# eVV_Power_Supply.net
KiCad netlist of a schematic drawn in Altium Designer
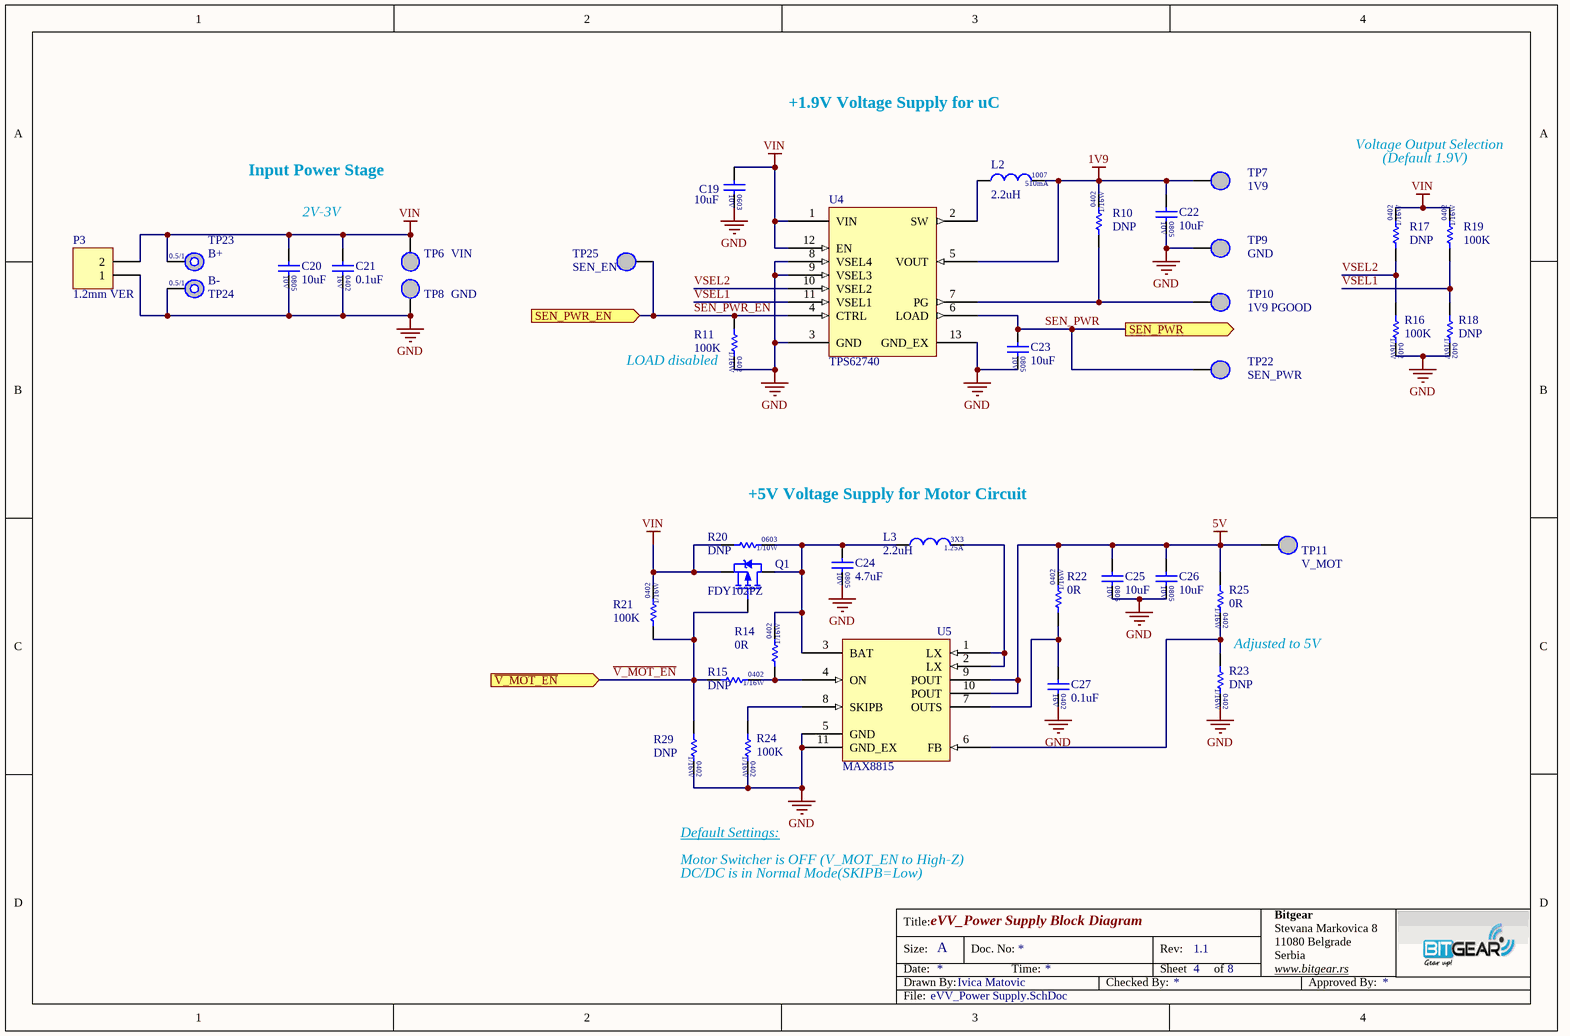
[diagram p0: eVV_Power Supply.SchDoc]

(export (version "E")
  (design (tool "Eeschema 10.0.6"))
  (components
    (comp (ref "C19")
      (value "10uF")
      (footprint "CAPC1608X95N")
      (description "Capacitor Ceramic 10uF 1608 (0603) 10V X5R 20%")
      (fields (field (name "MANUFACTURER") "Taiyo Yuden"))
      (libsource (lib "ecoVENTV") (part "Cap-1608 (0603) CER 10uF 10V X5R 20%"))
    )
    (comp (ref "C20")
      (value "10uF")
      (footprint "CAPC2012X145N")
      (description "Capacitor Ceramic 10uF 2012 (0805) 10V X5R 10%")
      (fields (field (name "MANUFACTURER") "TDK"))
      (libsource (lib "ecoVENTV") (part "Cap-2012 (0805) CER 10uF 10V X5R 10%"))
    )
    (comp (ref "C21")
      (value "0.1uF")
      (footprint "CAPC1005X60N")
      (description "CAP CER 0.1UF 0402 (1005) 16V X7R 10%")
      (fields (field (name "MANUFACTURER") "Murata Electronics North America"))
      (libsource (lib "ecoVENTV") (part "Cap-1005 (0402) CER 0.1UF 16V X7R 10%"))
    )
    (comp (ref "C22")
      (value "10uF")
      (footprint "CAPC2012X145N")
      (description "Capacitor Ceramic 10uF 2012 (0805) 10V X5R 10%")
      (fields (field (name "MANUFACTURER") "TDK"))
      (libsource (lib "ecoVENTV") (part "Cap-2012 (0805) CER 10uF 10V X5R 10%"))
    )
    (comp (ref "C23")
      (value "10uF")
      (footprint "CAPC2012X145N")
      (description "Capacitor Ceramic 10uF 2012 (0805) 10V X5R 10%")
      (fields (field (name "MANUFACTURER") "TDK"))
      (libsource (lib "ecoVENTV") (part "Cap-2012 (0805) CER 10uF 10V X5R 10%"))
    )
    (comp (ref "C24")
      (value "4.7uF")
      (footprint "CAPC2012X145N")
      (description "Capacitor Ceramic 4.7uF 2012 (0805) 10V X5R 10%")
      (fields (field (name "MANUFACTURER") "Samsung Electro-Mechanics America"))
      (libsource (lib "ecoVENTV") (part "Cap-2012 (0805) CER 4.7uF 10V X5R 10%"))
    )
    (comp (ref "C25")
      (value "10uF")
      (footprint "CAPC2012X145N")
      (description "Capacitor Ceramic 10uF 2012 (0805) 10V X5R 10%")
      (fields (field (name "MANUFACTURER") "TDK"))
      (libsource (lib "ecoVENTV") (part "Cap-2012 (0805) CER 10uF 10V X5R 10%"))
    )
    (comp (ref "C26")
      (value "10uF")
      (footprint "CAPC2012X145N")
      (description "Capacitor Ceramic 10uF 2012 (0805) 10V X5R 10%")
      (fields (field (name "MANUFACTURER") "TDK"))
      (libsource (lib "ecoVENTV") (part "Cap-2012 (0805) CER 10uF 10V X5R 10%"))
    )
    (comp (ref "C27")
      (value "0.1uF")
      (footprint "CAPC1005X60N")
      (description "CAP CER 0.1UF 0402 (1005) 16V X7R 10%")
      (fields (field (name "MANUFACTURER") "Murata Electronics North America"))
      (libsource (lib "ecoVENTV") (part "Cap-1005 (0402) CER 0.1UF 16V X7R 10%"))
    )
    (comp (ref "L2")
      (value "2.2uH")
      (footprint "INDC2518X200N")
      (description "Inductor 2.2uH 510mA 20% 1007")
      (fields (field (name "MANUFACTURER") "Taiyo Yuden"))
      (libsource (lib "ecoVENTV") (part "Ind-2518 (1007) 2.2uH 510mA 20%"))
    )
    (comp (ref "L3")
      (value "2.2uH")
      (footprint "IND_3.0X3.0X1.5MM")
      (description "Inductor 2.2uH 1.25A 20% 3.0X3.0mm")
      (fields (field (name "MANUFACTURER") "Murata Electronics North America"))
      (libsource (lib "ecoVENTV") (part "Ind-3.0X3.0mm 2.2uH 1.25A 20%"))
    )
    (comp (ref "P3")
      (value "1.2mm VER")
      (footprint "MOLEX_0781710002")
      (description "1.2mm pitch Pico-EZmate, Wire to Board, Vertical, with Locks, 1X2")
      (fields (field (name "MANUFACTURER") "Molex"))
      (libsource (lib "ecoVENTV") (part "Connector MOLEX Pico-EZmate 1X2 1.2mm"))
    )
    (comp (ref "Q1")
      (value "FDY102PZ")
      (footprint "SOT50P160X78-3N")
      (description "P-MOSFET Single 0.83A Low Vgs")
      (fields (field (name "MANUFACTURER") "Fairchild"))
      (libsource (lib "ecoVENTV") (part "FDY102PZ"))
    )
    (comp (ref "R10")
      (value "DNP")
      (footprint "RESC1005X40AN")
      (description "Res-1005 (0402) 100 KOhm 1/16W 1%")
      (fields (field (name "MANUFACTURER") "Vishay Dale"))
      (libsource (lib "ecoVENTV") (part "Res-1005 (0402) 100 KOhm 1/16W 1%"))
    )
    (comp (ref "R11")
      (value "100K")
      (footprint "RESC1005X40AN")
      (description "Res-1005 (0402) 100 KOhm 1/16W 1%")
      (fields (field (name "MANUFACTURER") "Vishay Dale"))
      (libsource (lib "ecoVENTV") (part "Res-1005 (0402) 100 KOhm 1/16W 1%"))
    )
    (comp (ref "R14")
      (value "0R")
      (footprint "RESC1005X40AN")
      (description "Res-1005 (0402) 0 Ohm 1/16W")
      (fields (field (name "MANUFACTURER") "Stackpole Electronics Inc"))
      (libsource (lib "ecoVENTV") (part "Res-1005 (0402) 0 Ohm 1/16W"))
    )
    (comp (ref "R15")
      (value "DNP")
      (footprint "RESC1005X40AN")
      (description "Res-1005 (0402) 0 Ohm 1/16W")
      (fields (field (name "MANUFACTURER") "Stackpole Electronics Inc"))
      (libsource (lib "ecoVENTV") (part "Res-1005 (0402) 0 Ohm 1/16W"))
    )
    (comp (ref "R16")
      (value "100K")
      (footprint "RESC1005X40AN")
      (description "Res-1005 (0402) 100 KOhm 1/16W 1%")
      (fields (field (name "MANUFACTURER") "Vishay Dale"))
      (libsource (lib "ecoVENTV") (part "Res-1005 (0402) 100 KOhm 1/16W 1%"))
    )
    (comp (ref "R17")
      (value "DNP")
      (footprint "RESC1005X40AN")
      (description "Res-1005 (0402) 100 KOhm 1/16W 1%")
      (fields (field (name "MANUFACTURER") "Vishay Dale"))
      (libsource (lib "ecoVENTV") (part "Res-1005 (0402) 100 KOhm 1/16W 1%"))
    )
    (comp (ref "R18")
      (value "DNP")
      (footprint "RESC1005X40AN")
      (description "Res-1005 (0402) 100 KOhm 1/16W 1%")
      (fields (field (name "MANUFACTURER") "Vishay Dale"))
      (libsource (lib "ecoVENTV") (part "Res-1005 (0402) 100 KOhm 1/16W 1%"))
    )
    (comp (ref "R19")
      (value "100K")
      (footprint "RESC1005X40AN")
      (description "Res-1005 (0402) 100 KOhm 1/16W 1%")
      (fields (field (name "MANUFACTURER") "Vishay Dale"))
      (libsource (lib "ecoVENTV") (part "Res-1005 (0402) 100 KOhm 1/16W 1%"))
    )
    (comp (ref "R20")
      (value "DNP")
      (footprint "RESC1608X84N")
      (description "Res-1608 (0603) 0 Ohm 1/10W")
      (fields (field (name "MANUFACTURER") "Samsung Electro-Mechanics America"))
      (libsource (lib "ecoVENTV") (part "Res-1608 (0603) 0 Ohm 1/10W"))
    )
    (comp (ref "R21")
      (value "100K")
      (footprint "RESC1005X40AN")
      (description "Res-1005 (0402) 100 KOhm 1/16W 1%")
      (fields (field (name "MANUFACTURER") "Vishay Dale"))
      (libsource (lib "ecoVENTV") (part "Res-1005 (0402) 100 KOhm 1/16W 1%"))
    )
    (comp (ref "R22")
      (value "0R")
      (footprint "RESC1005X40AN")
      (description "Res-1005 (0402) 0 Ohm 1/16W")
      (fields (field (name "MANUFACTURER") "Stackpole Electronics Inc"))
      (libsource (lib "ecoVENTV") (part "Res-1005 (0402) 0 Ohm 1/16W"))
    )
    (comp (ref "R23")
      (value "DNP")
      (footprint "RESC1005X40AN")
      (description "Res-1005 (0402) 105 KOhm 1/16W 1%")
      (fields (field (name "MANUFACTURER") "Vishay Dale"))
      (libsource (lib "ecoVENTV") (part "Res-1005 (0402) 105 KOhm 1/16W 1%"))
    )
    (comp (ref "R24")
      (value "100K")
      (footprint "RESC1005X40AN")
      (description "Res-1005 (0402) 100 KOhm 1/16W 1%")
      (fields (field (name "MANUFACTURER") "Vishay Dale"))
      (libsource (lib "ecoVENTV") (part "Res-1005 (0402) 100 KOhm 1/16W 1%"))
    )
    (comp (ref "R25")
      (value "0R")
      (footprint "RESC1005X40AN")
      (description "Res-1005 (0402) 0 Ohm 1/16W")
      (fields (field (name "MANUFACTURER") "Stackpole Electronics Inc"))
      (libsource (lib "ecoVENTV") (part "Res-1005 (0402) 0 Ohm 1/16W"))
    )
    (comp (ref "R29")
      (value "DNP")
      (footprint "RESC1005X40AN")
      (description "Res-1005 (0402) 100 KOhm 1/16W 1%")
      (fields (field (name "MANUFACTURER") "Vishay Dale"))
      (libsource (lib "ecoVENTV") (part "Res-1005 (0402) 100 KOhm 1/16W 1%"))
    )
    (comp (ref "TP6")
      (value "VIN")
      (footprint "TEST_POINT_1MM")
      (description "Test point")
      (libsource (lib "") (part "TP_2"))
    )
    (comp (ref "TP7")
      (value "1V9")
      (footprint "TEST_POINT_1MM")
      (description "Test point")
      (libsource (lib "ecoVENTV") (part "TP"))
    )
    (comp (ref "TP8")
      (value "GND")
      (footprint "TEST_POINT_1MM")
      (description "Test point")
      (libsource (lib "") (part "TP_3"))
    )
    (comp (ref "TP9")
      (value "GND")
      (footprint "TEST_POINT_1MM")
      (description "Test point")
      (libsource (lib "ecoVENTV") (part "TP"))
    )
    (comp (ref "TP10")
      (value "1V9 PGOOD")
      (footprint "TEST_POINT_1MM")
      (description "Test point")
      (libsource (lib "ecoVENTV") (part "TP"))
    )
    (comp (ref "TP11")
      (value "V_MOT")
      (footprint "TEST_POINT_1MM")
      (description "Test point")
      (libsource (lib "ecoVENTV") (part "TP"))
    )
    (comp (ref "TP22")
      (value "SEN_PWR")
      (footprint "TEST_POINT_1MM")
      (description "Test point")
      (libsource (lib "ecoVENTV") (part "TP"))
    )
    (comp (ref "TP23")
      (value "B+")
      (footprint "TEST_POINT_TH_1MM")
      (description "Test point Through Hole")
      (libsource (lib "ecoVENTV") (part "TP TH"))
    )
    (comp (ref "TP24")
      (value "B-")
      (footprint "TEST_POINT_TH_1MM")
      (description "Test point Through Hole")
      (libsource (lib "ecoVENTV") (part "TP TH"))
    )
    (comp (ref "TP25")
      (value "SEN_EN")
      (footprint "TEST_POINT_1MM")
      (description "Test point")
      (libsource (lib "") (part "TP_1"))
    )
    (comp (ref "U4")
      (value "TPS62740")
      (footprint "SON50P200X300X80-12-TP")
      (description "360nA Iq Step Down Converter for Low Power Applications")
      (fields (field (name "MANUFACTURER") "Texas Instruments"))
      (libsource (lib "ecoVENTV") (part "TPS62740"))
    )
    (comp (ref "U5")
      (value "MAX8815")
      (footprint "TQFN50P300X300X80-10N-TP")
      (description "100nA Iq Step Up Converter for Low Power Applications")
      (fields (field (name "MANUFACTURER") "Maxim Integrated"))
      (libsource (lib "ecoVENTV") (part "MAX8815"))
    )
  )
  (nets
    (net (code "1") (name "/SEN_PWR") (class "Default")
      (node (ref "C23") (pin "1") (pinfunction "1_1") (pintype "passive"))
      (node (ref "TP22") (pin "1") (pinfunction "1_1") (pintype "passive"))
      (node (ref "U4") (pin "6") (pinfunction "LOAD_6") (pintype "output"))
    )
    (net (code "2") (name "/SEN_PWR_EN") (class "Default")
      (node (ref "R11") (pin "2") (pinfunction "2_2") (pintype "passive"))
      (node (ref "TP25") (pin "1") (pinfunction "1_1") (pintype "passive"))
      (node (ref "U4") (pin "4") (pinfunction "CTRL_4") (pintype "input"))
    )
    (net (code "3") (name "/VSEL1") (class "Default")
      (node (ref "R18") (pin "2") (pinfunction "2_2") (pintype "passive"))
      (node (ref "R19") (pin "2") (pinfunction "2_2") (pintype "passive"))
      (node (ref "U4") (pin "11") (pinfunction "VSEL1_11") (pintype "input"))
    )
    (net (code "4") (name "/VSEL2") (class "Default")
      (node (ref "R16") (pin "2") (pinfunction "2_2") (pintype "passive"))
      (node (ref "R17") (pin "2") (pinfunction "2_2") (pintype "passive"))
      (node (ref "U4") (pin "10") (pinfunction "VSEL2_10") (pintype "input"))
    )
    (net (code "5") (name "/V_MOT_EN") (class "Default")
      (node (ref "Q1") (pin "1") (pinfunction "G_1") (pintype "passive"))
      (node (ref "R15") (pin "2") (pinfunction "2_2") (pintype "passive"))
      (node (ref "R21") (pin "2") (pinfunction "2_2") (pintype "passive"))
      (node (ref "R29") (pin "2") (pinfunction "2_2") (pintype "passive"))
    )
    (net (code "6") (name "1V9") (class "Default")
      (node (ref "C22") (pin "1") (pinfunction "1_1") (pintype "passive"))
      (node (ref "L2") (pin "2") (pinfunction "2_2") (pintype "passive"))
      (node (ref "R10") (pin "1") (pinfunction "1_1") (pintype "passive"))
      (node (ref "TP7") (pin "1") (pinfunction "1_1") (pintype "passive"))
      (node (ref "U4") (pin "5") (pinfunction "VOUT_5") (pintype "input"))
    )
    (net (code "7") (name "5V") (class "Default")
      (node (ref "C25") (pin "1") (pinfunction "1_1") (pintype "passive"))
      (node (ref "C26") (pin "1") (pinfunction "1_1") (pintype "passive"))
      (node (ref "R22") (pin "1") (pinfunction "1_1") (pintype "passive"))
      (node (ref "R25") (pin "2") (pinfunction "2_2") (pintype "passive"))
      (node (ref "TP11") (pin "1") (pinfunction "1_1") (pintype "passive"))
      (node (ref "U5") (pin "10") (pinfunction "POUT_10") (pintype "power_in"))
      (node (ref "U5") (pin "9") (pinfunction "POUT_9") (pintype "power_in"))
    )
    (net (code "8") (name "GND") (class "Default")
      (node (ref "C19") (pin "2") (pinfunction "2_2") (pintype "passive"))
      (node (ref "C20") (pin "2") (pinfunction "2_2") (pintype "passive"))
      (node (ref "C21") (pin "2") (pinfunction "2_2") (pintype "passive"))
      (node (ref "C22") (pin "2") (pinfunction "2_2") (pintype "passive"))
      (node (ref "C23") (pin "2") (pinfunction "2_2") (pintype "passive"))
      (node (ref "C24") (pin "2") (pinfunction "2_2") (pintype "passive"))
      (node (ref "C25") (pin "2") (pinfunction "2_2") (pintype "passive"))
      (node (ref "C26") (pin "2") (pinfunction "2_2") (pintype "passive"))
      (node (ref "C27") (pin "2") (pinfunction "2_2") (pintype "passive"))
      (node (ref "P3") (pin "1") (pinfunction "1_1") (pintype "passive"))
      (node (ref "R11") (pin "1") (pinfunction "1_1") (pintype "passive"))
      (node (ref "R16") (pin "1") (pinfunction "1_1") (pintype "passive"))
      (node (ref "R18") (pin "1") (pinfunction "1_1") (pintype "passive"))
      (node (ref "R23") (pin "1") (pinfunction "1_1") (pintype "passive"))
      (node (ref "R24") (pin "1") (pinfunction "1_1") (pintype "passive"))
      (node (ref "R29") (pin "1") (pinfunction "1_1") (pintype "passive"))
      (node (ref "TP24") (pin "1") (pinfunction "1_1") (pintype "passive"))
      (node (ref "TP8") (pin "1") (pinfunction "1_1") (pintype "passive"))
      (node (ref "TP9") (pin "1") (pinfunction "1_1") (pintype "passive"))
      (node (ref "U4") (pin "13") (pinfunction "GND_EX_13") (pintype "power_in"))
      (node (ref "U4") (pin "3") (pinfunction "GND_3") (pintype "power_in"))
      (node (ref "U4") (pin "8") (pinfunction "VSEL4_8") (pintype "input"))
      (node (ref "U4") (pin "9") (pinfunction "VSEL3_9") (pintype "input"))
      (node (ref "U5") (pin "11") (pinfunction "GND_EX_11") (pintype "power_in"))
      (node (ref "U5") (pin "5") (pinfunction "GND_5") (pintype "power_in"))
    )
    (net (code "9") (name "Net-(L3-Pad2)") (class "Default")
      (node (ref "L3") (pin "2") (pinfunction "2_2") (pintype "passive"))
      (node (ref "U5") (pin "1") (pinfunction "LX_1") (pintype "input"))
      (node (ref "U5") (pin "2") (pinfunction "LX_2") (pintype "input"))
    )
    (net (code "10") (name "Net-(Q1-D)") (class "Default")
      (node (ref "C24") (pin "1") (pinfunction "1_1") (pintype "passive"))
      (node (ref "L3") (pin "1") (pinfunction "1_1") (pintype "passive"))
      (node (ref "Q1") (pin "3") (pinfunction "D_3") (pintype "passive"))
      (node (ref "R14") (pin "1") (pinfunction "1_1") (pintype "passive"))
      (node (ref "R20") (pin "1") (pinfunction "1_1") (pintype "passive"))
      (node (ref "U5") (pin "3") (pinfunction "BAT_3") (pintype "power_in"))
    )
    (net (code "11") (name "Net-(U4-PG)") (class "Default")
      (node (ref "R10") (pin "2") (pinfunction "2_2") (pintype "passive"))
      (node (ref "TP10") (pin "1") (pinfunction "1_1") (pintype "passive"))
      (node (ref "U4") (pin "7") (pinfunction "PG_7") (pintype "output"))
    )
    (net (code "12") (name "Net-(U4-SW)") (class "Default")
      (node (ref "L2") (pin "1") (pinfunction "1_1") (pintype "passive"))
      (node (ref "U4") (pin "2") (pinfunction "SW_2") (pintype "output"))
    )
    (net (code "13") (name "Net-(U5-FB)") (class "Default")
      (node (ref "R23") (pin "2") (pinfunction "2_2") (pintype "passive"))
      (node (ref "R25") (pin "1") (pinfunction "1_1") (pintype "passive"))
      (node (ref "U5") (pin "6") (pinfunction "FB_6") (pintype "input"))
    )
    (net (code "14") (name "Net-(U5-ON)") (class "Default")
      (node (ref "R14") (pin "2") (pinfunction "2_2") (pintype "passive"))
      (node (ref "R15") (pin "1") (pinfunction "1_1") (pintype "passive"))
      (node (ref "U5") (pin "4") (pinfunction "ON_4") (pintype "input"))
    )
    (net (code "15") (name "Net-(U5-OUTS)") (class "Default")
      (node (ref "C27") (pin "1") (pinfunction "1_1") (pintype "passive"))
      (node (ref "R22") (pin "2") (pinfunction "2_2") (pintype "passive"))
      (node (ref "U5") (pin "7") (pinfunction "OUTS_7") (pintype "power_in"))
    )
    (net (code "16") (name "Net-(U5-SKIPB)") (class "Default")
      (node (ref "R24") (pin "2") (pinfunction "2_2") (pintype "passive"))
      (node (ref "U5") (pin "8") (pinfunction "SKIPB_8") (pintype "input"))
    )
    (net (code "17") (name "VIN") (class "Default")
      (node (ref "C19") (pin "1") (pinfunction "1_1") (pintype "passive"))
      (node (ref "C20") (pin "1") (pinfunction "1_1") (pintype "passive"))
      (node (ref "C21") (pin "1") (pinfunction "1_1") (pintype "passive"))
      (node (ref "P3") (pin "2") (pinfunction "2_2") (pintype "passive"))
      (node (ref "Q1") (pin "2") (pinfunction "S_2") (pintype "passive"))
      (node (ref "R17") (pin "1") (pinfunction "1_1") (pintype "passive"))
      (node (ref "R19") (pin "1") (pinfunction "1_1") (pintype "passive"))
      (node (ref "R20") (pin "2") (pinfunction "2_2") (pintype "passive"))
      (node (ref "R21") (pin "1") (pinfunction "1_1") (pintype "passive"))
      (node (ref "TP23") (pin "1") (pinfunction "1_1") (pintype "passive"))
      (node (ref "TP6") (pin "1") (pinfunction "1_1") (pintype "passive"))
      (node (ref "U4") (pin "1") (pinfunction "VIN_1") (pintype "power_in"))
      (node (ref "U4") (pin "12") (pinfunction "EN_12") (pintype "input"))
    )
  )
)
